# design.net
KiCad netlist of a schematic drawn in Altium Designer
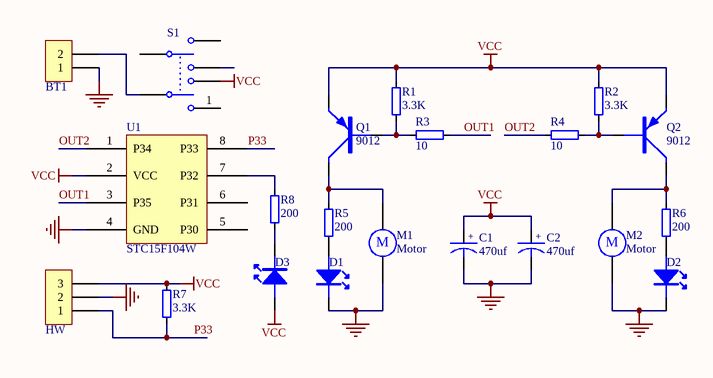
[diagram p0: 红外遥控小车.SchDoc]

(export (version "E")
  (design (tool "Eeschema 10.0.6"))
  (components
    (comp (ref "BT1")
      (value "CON2")
      (footprint "CON2--5.08")
      (description "Connector")
      (libsource (lib "Backup of 元件") (part "CON2"))
    )
    (comp (ref "C1")
      (value "CAPACITOR POL")
      (footprint "电容D=8mm")
      (description "Capacitor")
      (fields (field (name "ALTIUM_UNNAMED_1") "470uf"))
      (libsource (lib "MyInt_Lib") (part "CAPACITOR POL"))
    )
    (comp (ref "C2")
      (value "CAPACITOR POL")
      (footprint "电容D=8mm")
      (description "Capacitor")
      (fields (field (name "ALTIUM_UNNAMED_1") "470uf"))
      (libsource (lib "MyInt_Lib") (part "CAPACITOR POL"))
    )
    (comp (ref "D1") (value "LED") (footprint "DIODE0.1") (libsource (lib "DIODE") (part "LED")))
    (comp (ref "D2") (value "LED") (footprint "DIODE0.1") (libsource (lib "DIODE") (part "LED")))
    (comp (ref "D3") (value "LED") (footprint "DIODE0.1") (libsource (lib "DIODE") (part "LED")))
    (comp (ref "HW")
      (value "CON3")
      (footprint "红外接收头")
      (description "Connector")
      (libsource (lib "复件 Previous Backup of 元件") (part "CON3"))
    )
    (comp (ref "M1")
      (value "Motor")
      (footprint "CON2--5.08")
      (description "Motor, General Kind")
      (fields (field (name "PUBLISHER") "Altium Limited"))
      (libsource (lib "Miscellaneous Devices") (part "Motor"))
    )
    (comp (ref "M2")
      (value "Motor")
      (footprint "CON2--5.08")
      (description "Motor, General Kind")
      (fields (field (name "PUBLISHER") "Altium Limited"))
      (libsource (lib "Miscellaneous Devices") (part "Motor"))
    )
    (comp (ref "Q1")
      (value "9012")
      (footprint "8050-TO-92")
      (description "PNP Transistor")
      (libsource (lib "Backup of 元件") (part "8550"))
    )
    (comp (ref "Q2")
      (value "9012")
      (footprint "8050-TO-92")
      (description "PNP Transistor")
      (libsource (lib "Backup of 元件") (part "8550"))
    )
    (comp (ref "R1")
      (value "RES")
      (footprint "RES-0.25W")
      (fields (field (name "ALTIUM_UNNAMED_1") "3.3K"))
      (libsource (lib "MyInt_Lib") (part "RES"))
    )
    (comp (ref "R2")
      (value "RES")
      (footprint "RES-0.25W")
      (fields (field (name "ALTIUM_UNNAMED_1") "3.3K"))
      (libsource (lib "MyInt_Lib") (part "RES"))
    )
    (comp (ref "R3")
      (value "RES")
      (footprint "RES-0.25W")
      (fields (field (name "ALTIUM_UNNAMED_1") "10"))
      (libsource (lib "MyInt_Lib") (part "RES"))
    )
    (comp (ref "R4")
      (value "RES")
      (footprint "RES-0.25W")
      (fields (field (name "ALTIUM_UNNAMED_1") "10"))
      (libsource (lib "MyInt_Lib") (part "RES"))
    )
    (comp (ref "R5")
      (value "RES")
      (footprint "RES-0.25W")
      (fields (field (name "ALTIUM_UNNAMED_1") "200"))
      (libsource (lib "MyInt_Lib") (part "RES"))
    )
    (comp (ref "R6")
      (value "RES")
      (footprint "RES-0.25W")
      (fields (field (name "ALTIUM_UNNAMED_1") "200"))
      (libsource (lib "MyInt_Lib") (part "RES"))
    )
    (comp (ref "R7")
      (value "RES")
      (footprint "RES-0.25W")
      (fields (field (name "ALTIUM_UNNAMED_1") "3.3K"))
      (libsource (lib "MyInt_Lib") (part "RES"))
    )
    (comp (ref "R8")
      (value "RES")
      (footprint "RES-0.25W")
      (fields (field (name "ALTIUM_UNNAMED_1") "200"))
      (libsource (lib "MyInt_Lib") (part "RES"))
    )
    (comp (ref "S1")
      (value "SW-DPDT")
      (footprint "自锁6*6")
      (description "Double-Pole, Double-Throw Switch")
      (fields (field (name "PUBLISHER") "Altium Limited"))
      (libsource (lib "Miscellaneous Devices") (part "SW-DPDT"))
    )
    (comp (ref "U1") (value "STC15F104W") (footprint "DIP8") (libsource (lib "DIP8") (part "DIP8")))
  )
  (nets
    (net (code "1") (name "/OUT1") (class "Default")
      (node (ref "R3") (pin "1") (pinfunction "1_1") (pintype "passive"))
      (node (ref "U1") (pin "3") (pinfunction "P35_3") (pintype "passive"))
    )
    (net (code "2") (name "/OUT2") (class "Default")
      (node (ref "R4") (pin "2") (pinfunction "2_2") (pintype "passive"))
      (node (ref "U1") (pin "1") (pinfunction "P34_1") (pintype "passive"))
    )
    (net (code "3") (name "/P33") (class "Default")
      (node (ref "HW") (pin "1") (pinfunction "1_1") (pintype "passive"))
      (node (ref "R7") (pin "1") (pinfunction "1_1") (pintype "passive"))
      (node (ref "U1") (pin "8") (pinfunction "P33_8") (pintype "passive"))
    )
    (net (code "4") (name "GND") (class "Default")
      (node (ref "BT1") (pin "1") (pinfunction "1_1") (pintype "passive"))
      (node (ref "C1") (pin "2") (pinfunction "2_2") (pintype "passive"))
      (node (ref "C2") (pin "2") (pinfunction "2_2") (pintype "passive"))
      (node (ref "D1") (pin "2") (pinfunction "2_2") (pintype "passive"))
      (node (ref "D2") (pin "2") (pinfunction "2_2") (pintype "passive"))
      (node (ref "HW") (pin "2") (pinfunction "2_2") (pintype "passive"))
      (node (ref "M1") (pin "2") (pinfunction "2_2") (pintype "passive"))
      (node (ref "M2") (pin "2") (pinfunction "2_2") (pintype "passive"))
      (node (ref "U1") (pin "4") (pinfunction "GND_4") (pintype "passive"))
    )
    (net (code "5") (name "Net-(BT1-Pad2)") (class "Default")
      (node (ref "BT1") (pin "2") (pinfunction "2_2") (pintype "passive"))
      (node (ref "S1") (pin "3") (pintype "passive"))
    )
    (net (code "6") (name "Net-(D1-Pad1)") (class "Default")
      (node (ref "D1") (pin "1") (pinfunction "1_1") (pintype "passive"))
      (node (ref "R5") (pin "1") (pinfunction "1_1") (pintype "passive"))
    )
    (net (code "7") (name "Net-(D2-Pad1)") (class "Default")
      (node (ref "D2") (pin "1") (pinfunction "1_1") (pintype "passive"))
      (node (ref "R6") (pin "1") (pinfunction "1_1") (pintype "passive"))
    )
    (net (code "8") (name "Net-(D3-Pad2)") (class "Default")
      (node (ref "D3") (pin "2") (pinfunction "2_2") (pintype "passive"))
      (node (ref "R8") (pin "2") (pinfunction "2_2") (pintype "passive"))
    )
    (net (code "9") (name "Net-(Q1-B)") (class "Default")
      (node (ref "Q1") (pin "2") (pinfunction "B_2") (pintype "passive"))
      (node (ref "R1") (pin "1") (pinfunction "1_1") (pintype "passive"))
      (node (ref "R3") (pin "2") (pinfunction "2_2") (pintype "passive"))
    )
    (net (code "10") (name "Net-(Q1-C)") (class "Default")
      (node (ref "M1") (pin "1") (pinfunction "1_1") (pintype "passive"))
      (node (ref "Q1") (pin "3") (pinfunction "C_3") (pintype "passive"))
      (node (ref "R5") (pin "2") (pinfunction "2_2") (pintype "passive"))
    )
    (net (code "11") (name "Net-(Q2-B)") (class "Default")
      (node (ref "Q2") (pin "2") (pinfunction "B_2") (pintype "passive"))
      (node (ref "R2") (pin "1") (pinfunction "1_1") (pintype "passive"))
      (node (ref "R4") (pin "1") (pinfunction "1_1") (pintype "passive"))
    )
    (net (code "12") (name "Net-(Q2-C)") (class "Default")
      (node (ref "M2") (pin "1") (pinfunction "1_1") (pintype "passive"))
      (node (ref "Q2") (pin "3") (pinfunction "C_3") (pintype "passive"))
      (node (ref "R6") (pin "2") (pinfunction "2_2") (pintype "passive"))
    )
    (net (code "13") (name "Net-(U1-P32)") (class "Default")
      (node (ref "R8") (pin "1") (pinfunction "1_1") (pintype "passive"))
      (node (ref "U1") (pin "7") (pinfunction "P32_7") (pintype "passive"))
    )
    (net (code "14") (name "VCC") (class "Default")
      (node (ref "C1") (pin "1") (pinfunction "1_1") (pintype "passive"))
      (node (ref "C2") (pin "1") (pinfunction "1_1") (pintype "passive"))
      (node (ref "D3") (pin "1") (pinfunction "1_1") (pintype "passive"))
      (node (ref "HW") (pin "3") (pinfunction "3_3") (pintype "passive"))
      (node (ref "Q1") (pin "1") (pinfunction "E_1") (pintype "passive"))
      (node (ref "Q2") (pin "1") (pinfunction "E_1") (pintype "passive"))
      (node (ref "R1") (pin "2") (pinfunction "2_2") (pintype "passive"))
      (node (ref "R2") (pin "2") (pinfunction "2_2") (pintype "passive"))
      (node (ref "R7") (pin "2") (pinfunction "2_2") (pintype "passive"))
      (node (ref "S1") (pin "2") (pintype "passive"))
      (node (ref "U1") (pin "2") (pinfunction "VCC_2") (pintype "passive"))
    )
    (net (code "15") (name "unconnected-(S1-Pad1)") (class "Default")
      (node (ref "S1") (pin "1") (pintype "passive"))
    )
    (net (code "16") (name "unconnected-(S1-Pad4)") (class "Default")
      (node (ref "S1") (pin "4") (pintype "passive"))
    )
    (net (code "17") (name "unconnected-(S1-Pad5)") (class "Default")
      (node (ref "S1") (pin "5") (pintype "passive"))
    )
    (net (code "18") (name "unconnected-(S1-Pad6)") (class "Default")
      (node (ref "S1") (pin "6") (pintype "passive"))
    )
    (net (code "19") (name "unconnected-(U1-P30-Pad5)") (class "Default")
      (node (ref "U1") (pin "5") (pinfunction "P30_5") (pintype "passive"))
    )
    (net (code "20") (name "unconnected-(U1-P31-Pad6)") (class "Default")
      (node (ref "U1") (pin "6") (pinfunction "P31_6") (pintype "passive"))
    )
  )
)
